# 6ButtonSMD.net
KiCad netlist of a schematic drawn in EAGLE
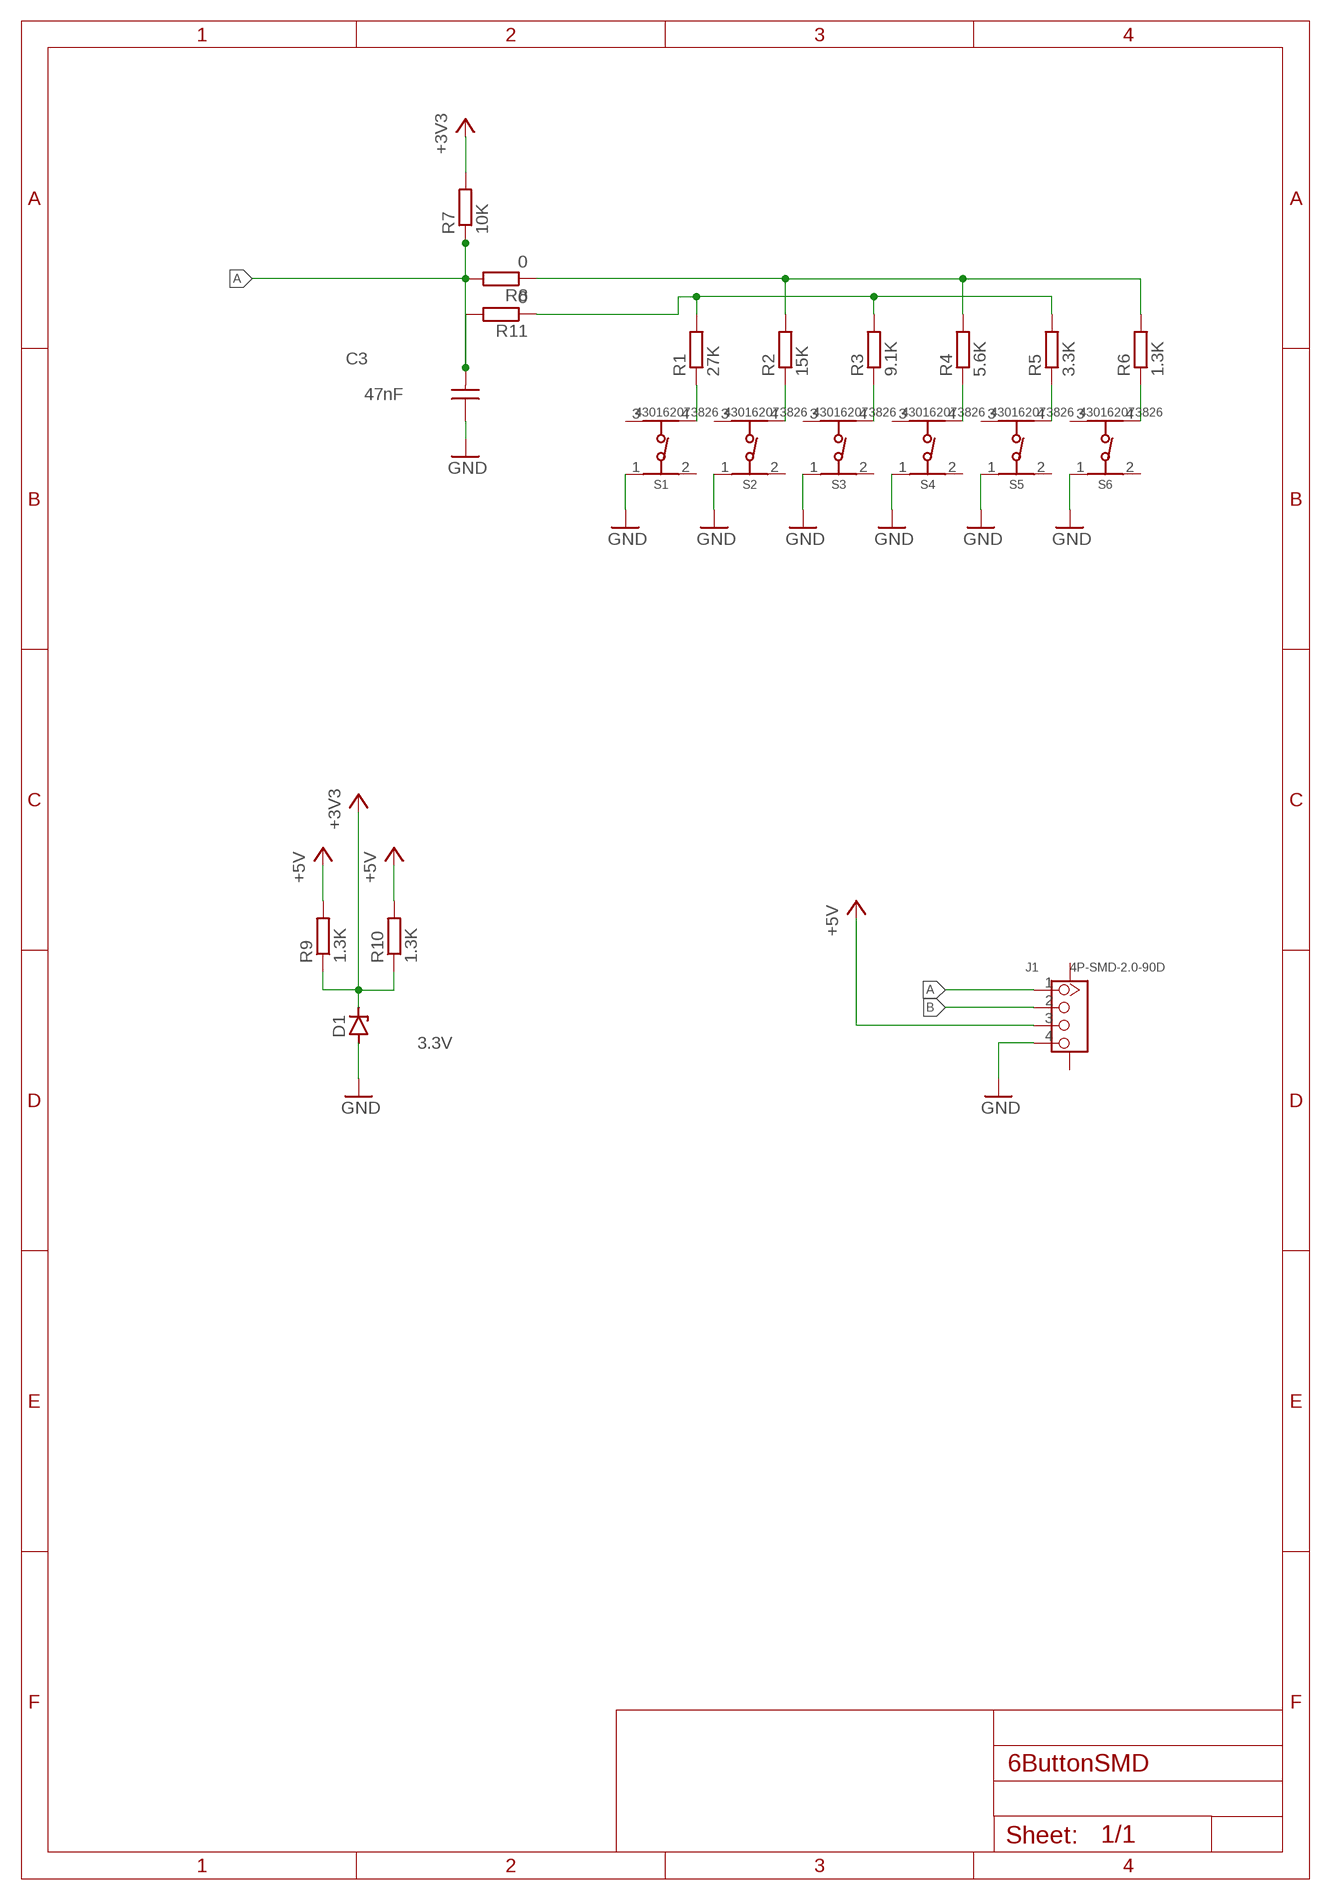
[diagram p0: schematic, sheet 1]

(export (version "E")
  (design (tool "Eeschema 10.0.6"))
  (components
    (comp (ref "C3")
      (value "47nF")
      (footprint "eagle-import:WCAP-CSGP_1206_H0.8")
      (libsource (lib "eagle-import") (part "WCAP-CSGP_1206_H0.8_50V(DC)_885012208085"))
    )
    (comp (ref "D1")
      (value "3.3V")
      (footprint "eagle-import:SOD80C")
      (libsource (lib "eagle-import") (part "ZENER-DIODESOD80C"))
    )
    (comp (ref "J1")
      (value "4P-SMD-2.0-90D")
      (footprint "eagle-import:HW4-SMD-2.0-90D")
      (libsource (lib "eagle-import") (part "GROVE-CONNECTOR-SMD-90D(4+2P-2.0)"))
    )
    (comp (ref "R1")
      (value "27K")
      (footprint "eagle-import:R1206")
      (libsource (lib "eagle-import") (part "R-EU_R1206"))
    )
    (comp (ref "R2")
      (value "15K")
      (footprint "eagle-import:R1206")
      (libsource (lib "eagle-import") (part "R-EU_R1206"))
    )
    (comp (ref "R3")
      (value "9.1K")
      (footprint "eagle-import:R1206")
      (libsource (lib "eagle-import") (part "R-EU_R1206"))
    )
    (comp (ref "R4")
      (value "5.6K")
      (footprint "eagle-import:R1206")
      (libsource (lib "eagle-import") (part "R-EU_R1206"))
    )
    (comp (ref "R5")
      (value "3.3K")
      (footprint "eagle-import:R1206")
      (libsource (lib "eagle-import") (part "R-EU_R1206"))
    )
    (comp (ref "R6")
      (value "1.3K")
      (footprint "eagle-import:R1206")
      (libsource (lib "eagle-import") (part "R-EU_R1206"))
    )
    (comp (ref "R7")
      (value "10K")
      (footprint "eagle-import:R1206")
      (libsource (lib "eagle-import") (part "R-EU_R1206"))
    )
    (comp (ref "R8")
      (value "0")
      (footprint "eagle-import:R1206")
      (libsource (lib "eagle-import") (part "R-EU_R1206"))
    )
    (comp (ref "R9")
      (value "1.3K")
      (footprint "eagle-import:R1206")
      (libsource (lib "eagle-import") (part "R-EU_R1206"))
    )
    (comp (ref "R10")
      (value "1.3K")
      (footprint "eagle-import:R1206")
      (libsource (lib "eagle-import") (part "R-EU_R1206"))
    )
    (comp (ref "R11")
      (value "0")
      (footprint "eagle-import:R1206")
      (libsource (lib "eagle-import") (part "R-EU_R1206"))
    )
    (comp (ref "S1")
      (value "430162073826")
      (footprint "eagle-import:430162073826")
      (libsource (lib "eagle-import") (part "430162073826"))
    )
    (comp (ref "S2")
      (value "430162073826")
      (footprint "eagle-import:430162073826")
      (libsource (lib "eagle-import") (part "430162073826"))
    )
    (comp (ref "S3")
      (value "430162073826")
      (footprint "eagle-import:430162073826")
      (libsource (lib "eagle-import") (part "430162073826"))
    )
    (comp (ref "S4")
      (value "430162073826")
      (footprint "eagle-import:430162073826")
      (libsource (lib "eagle-import") (part "430162073826"))
    )
    (comp (ref "S5")
      (value "430162073826")
      (footprint "eagle-import:430162073826")
      (libsource (lib "eagle-import") (part "430162073826"))
    )
    (comp (ref "S6")
      (value "430162073826")
      (footprint "eagle-import:430162073826")
      (libsource (lib "eagle-import") (part "430162073826"))
    )
  )
  (nets
    (net (code "1") (name "+3V3") (class "Default")
      (node (ref "D1") (pin "C") (pinfunction "C_C") (pintype "passive"))
      (node (ref "R10") (pin "1") (pinfunction "1_1") (pintype "passive"))
      (node (ref "R7") (pin "2") (pinfunction "2_2") (pintype "passive"))
      (node (ref "R9") (pin "1") (pinfunction "1_1") (pintype "passive"))
    )
    (net (code "2") (name "+5V") (class "Default")
      (node (ref "J1") (pin "3") (pinfunction "3_3") (pintype "bidirectional"))
      (node (ref "R10") (pin "2") (pinfunction "2_2") (pintype "passive"))
      (node (ref "R9") (pin "2") (pinfunction "2_2") (pintype "passive"))
    )
    (net (code "3") (name "A") (class "Default")
      (node (ref "C3") (pin "2") (pinfunction "2_2") (pintype "passive"))
      (node (ref "J1") (pin "1") (pinfunction "1_1") (pintype "bidirectional"))
      (node (ref "R11") (pin "2") (pinfunction "2_2") (pintype "passive"))
      (node (ref "R7") (pin "1") (pinfunction "1_1") (pintype "passive"))
      (node (ref "R8") (pin "2") (pinfunction "2_2") (pintype "passive"))
    )
    (net (code "4") (name "B") (class "Default")
      (node (ref "J1") (pin "2") (pinfunction "2_2") (pintype "bidirectional"))
    )
    (net (code "5") (name "GND") (class "Default")
      (node (ref "C3") (pin "1") (pinfunction "1_1") (pintype "passive"))
      (node (ref "D1") (pin "A") (pinfunction "A_A") (pintype "passive"))
      (node (ref "J1") (pin "4") (pinfunction "4_4") (pintype "bidirectional"))
      (node (ref "S1") (pin "1") (pinfunction "1_1") (pintype "passive"))
      (node (ref "S2") (pin "1") (pinfunction "1_1") (pintype "passive"))
      (node (ref "S3") (pin "1") (pinfunction "1_1") (pintype "passive"))
      (node (ref "S4") (pin "1") (pinfunction "1_1") (pintype "passive"))
      (node (ref "S5") (pin "1") (pinfunction "1_1") (pintype "passive"))
      (node (ref "S6") (pin "1") (pinfunction "1_1") (pintype "passive"))
    )
    (net (code "6") (name "Net-(R1-Pad1)") (class "Default")
      (node (ref "R1") (pin "1") (pinfunction "1_1") (pintype "passive"))
      (node (ref "S1") (pin "4") (pinfunction "4_4") (pintype "passive"))
    )
    (net (code "7") (name "Net-(R1-Pad2)") (class "Default")
      (node (ref "R1") (pin "2") (pinfunction "2_2") (pintype "passive"))
      (node (ref "R11") (pin "1") (pinfunction "1_1") (pintype "passive"))
      (node (ref "R3") (pin "2") (pinfunction "2_2") (pintype "passive"))
      (node (ref "R5") (pin "2") (pinfunction "2_2") (pintype "passive"))
    )
    (net (code "8") (name "Net-(R2-Pad1)") (class "Default")
      (node (ref "R2") (pin "1") (pinfunction "1_1") (pintype "passive"))
      (node (ref "S2") (pin "4") (pinfunction "4_4") (pintype "passive"))
    )
    (net (code "9") (name "Net-(R2-Pad2)") (class "Default")
      (node (ref "R2") (pin "2") (pinfunction "2_2") (pintype "passive"))
      (node (ref "R4") (pin "2") (pinfunction "2_2") (pintype "passive"))
      (node (ref "R6") (pin "2") (pinfunction "2_2") (pintype "passive"))
      (node (ref "R8") (pin "1") (pinfunction "1_1") (pintype "passive"))
    )
    (net (code "10") (name "Net-(R3-Pad1)") (class "Default")
      (node (ref "R3") (pin "1") (pinfunction "1_1") (pintype "passive"))
      (node (ref "S3") (pin "4") (pinfunction "4_4") (pintype "passive"))
    )
    (net (code "11") (name "Net-(R4-Pad1)") (class "Default")
      (node (ref "R4") (pin "1") (pinfunction "1_1") (pintype "passive"))
      (node (ref "S4") (pin "4") (pinfunction "4_4") (pintype "passive"))
    )
    (net (code "12") (name "Net-(R5-Pad1)") (class "Default")
      (node (ref "R5") (pin "1") (pinfunction "1_1") (pintype "passive"))
      (node (ref "S5") (pin "4") (pinfunction "4_4") (pintype "passive"))
    )
    (net (code "13") (name "Net-(R6-Pad1)") (class "Default")
      (node (ref "R6") (pin "1") (pinfunction "1_1") (pintype "passive"))
      (node (ref "S6") (pin "4") (pinfunction "4_4") (pintype "passive"))
    )
    (net (code "14") (name "unconnected-(J1-PadSS1)") (class "Default")
      (node (ref "J1") (pin "SS1") (pinfunction "SS1_SS1") (pintype "bidirectional"))
    )
    (net (code "15") (name "unconnected-(J1-PadSS2)") (class "Default")
      (node (ref "J1") (pin "SS2") (pinfunction "SS2_SS2") (pintype "bidirectional"))
    )
    (net (code "16") (name "unconnected-(S1-2-Pad3)") (class "Default")
      (node (ref "S1") (pin "3") (pinfunction "2_3") (pintype "passive"))
    )
    (net (code "17") (name "unconnected-(S1-3-Pad2)") (class "Default")
      (node (ref "S1") (pin "2") (pinfunction "3_2") (pintype "passive"))
    )
    (net (code "18") (name "unconnected-(S2-2-Pad3)") (class "Default")
      (node (ref "S2") (pin "3") (pinfunction "2_3") (pintype "passive"))
    )
    (net (code "19") (name "unconnected-(S2-3-Pad2)") (class "Default")
      (node (ref "S2") (pin "2") (pinfunction "3_2") (pintype "passive"))
    )
    (net (code "20") (name "unconnected-(S3-2-Pad3)") (class "Default")
      (node (ref "S3") (pin "3") (pinfunction "2_3") (pintype "passive"))
    )
    (net (code "21") (name "unconnected-(S3-3-Pad2)") (class "Default")
      (node (ref "S3") (pin "2") (pinfunction "3_2") (pintype "passive"))
    )
    (net (code "22") (name "unconnected-(S4-2-Pad3)") (class "Default")
      (node (ref "S4") (pin "3") (pinfunction "2_3") (pintype "passive"))
    )
    (net (code "23") (name "unconnected-(S4-3-Pad2)") (class "Default")
      (node (ref "S4") (pin "2") (pinfunction "3_2") (pintype "passive"))
    )
    (net (code "24") (name "unconnected-(S5-2-Pad3)") (class "Default")
      (node (ref "S5") (pin "3") (pinfunction "2_3") (pintype "passive"))
    )
    (net (code "25") (name "unconnected-(S5-3-Pad2)") (class "Default")
      (node (ref "S5") (pin "2") (pinfunction "3_2") (pintype "passive"))
    )
    (net (code "26") (name "unconnected-(S6-2-Pad3)") (class "Default")
      (node (ref "S6") (pin "3") (pinfunction "2_3") (pintype "passive"))
    )
    (net (code "27") (name "unconnected-(S6-3-Pad2)") (class "Default")
      (node (ref "S6") (pin "2") (pinfunction "3_2") (pintype "passive"))
    )
  )
)
